# AutoReverse.net
KiCad netlist of a schematic drawn in Altium Designer
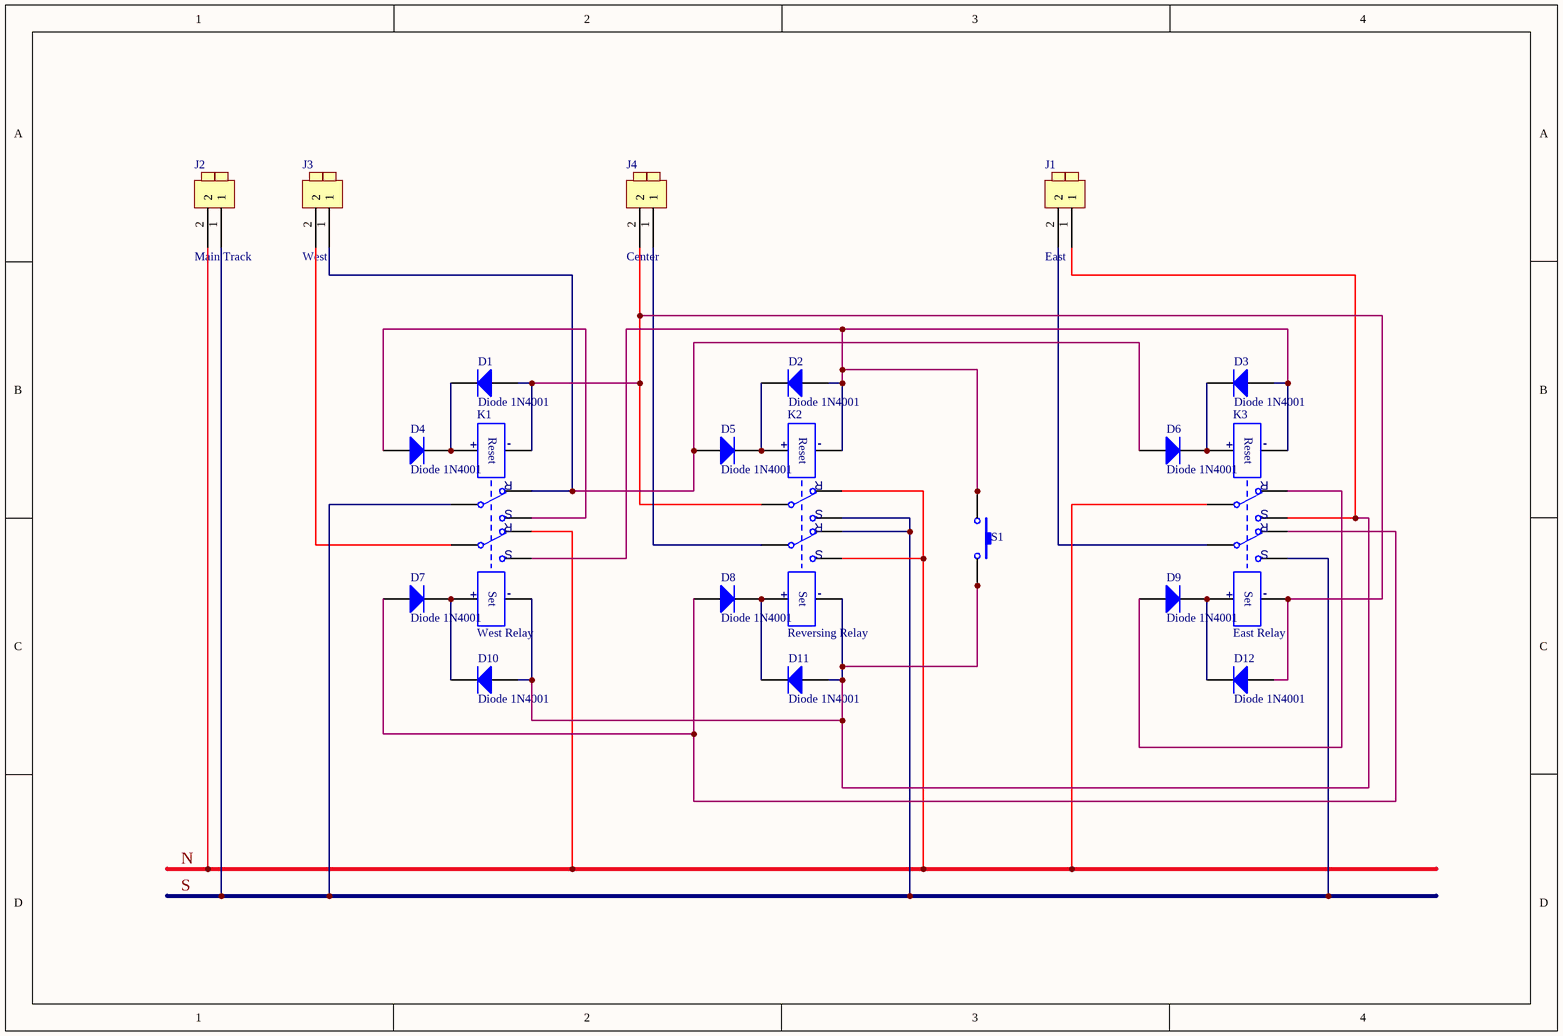
[diagram p0: AutoReverse.SchDoc]

(export (version "E")
  (design (tool "Eeschema 10.0.6"))
  (components
    (comp (ref "D1")
      (value "Diode 1N4001")
      (footprint "AXIAL-0.3")
      (description "1 Amp General Purpose Rectifier")
      (fields (field (name "PUBLISHER") "Altium Limited"))
      (libsource (lib "Miscellaneous Devices") (part "Diode 1N4001"))
    )
    (comp (ref "D2")
      (value "Diode 1N4001")
      (footprint "AXIAL-0.3")
      (description "1 Amp General Purpose Rectifier")
      (fields (field (name "PUBLISHER") "Altium Limited"))
      (libsource (lib "Miscellaneous Devices") (part "Diode 1N4001"))
    )
    (comp (ref "D3")
      (value "Diode 1N4001")
      (footprint "AXIAL-0.3")
      (description "1 Amp General Purpose Rectifier")
      (fields (field (name "PUBLISHER") "Altium Limited"))
      (libsource (lib "Miscellaneous Devices") (part "Diode 1N4001"))
    )
    (comp (ref "D4")
      (value "Diode 1N4001")
      (footprint "AXIAL-0.3")
      (description "1 Amp General Purpose Rectifier")
      (fields (field (name "PUBLISHER") "Altium Limited"))
      (libsource (lib "Miscellaneous Devices") (part "Diode 1N4001"))
    )
    (comp (ref "D5")
      (value "Diode 1N4001")
      (footprint "AXIAL-0.3")
      (description "1 Amp General Purpose Rectifier")
      (fields (field (name "PUBLISHER") "Altium Limited"))
      (libsource (lib "Miscellaneous Devices") (part "Diode 1N4001"))
    )
    (comp (ref "D6")
      (value "Diode 1N4001")
      (footprint "AXIAL-0.3")
      (description "1 Amp General Purpose Rectifier")
      (fields (field (name "PUBLISHER") "Altium Limited"))
      (libsource (lib "Miscellaneous Devices") (part "Diode 1N4001"))
    )
    (comp (ref "D7")
      (value "Diode 1N4001")
      (footprint "AXIAL-0.3")
      (description "1 Amp General Purpose Rectifier")
      (fields (field (name "PUBLISHER") "Altium Limited"))
      (libsource (lib "Miscellaneous Devices") (part "Diode 1N4001"))
    )
    (comp (ref "D8")
      (value "Diode 1N4001")
      (footprint "AXIAL-0.3")
      (description "1 Amp General Purpose Rectifier")
      (fields (field (name "PUBLISHER") "Altium Limited"))
      (libsource (lib "Miscellaneous Devices") (part "Diode 1N4001"))
    )
    (comp (ref "D9")
      (value "Diode 1N4001")
      (footprint "AXIAL-0.3")
      (description "1 Amp General Purpose Rectifier")
      (fields (field (name "PUBLISHER") "Altium Limited"))
      (libsource (lib "Miscellaneous Devices") (part "Diode 1N4001"))
    )
    (comp (ref "D10")
      (value "Diode 1N4001")
      (footprint "AXIAL-0.3")
      (description "1 Amp General Purpose Rectifier")
      (fields (field (name "PUBLISHER") "Altium Limited"))
      (libsource (lib "Miscellaneous Devices") (part "Diode 1N4001"))
    )
    (comp (ref "D11")
      (value "Diode 1N4001")
      (footprint "AXIAL-0.3")
      (description "1 Amp General Purpose Rectifier")
      (fields (field (name "PUBLISHER") "Altium Limited"))
      (libsource (lib "Miscellaneous Devices") (part "Diode 1N4001"))
    )
    (comp (ref "D12")
      (value "Diode 1N4001")
      (footprint "AXIAL-0.3")
      (description "1 Amp General Purpose Rectifier")
      (fields (field (name "PUBLISHER") "Altium Limited"))
      (libsource (lib "Miscellaneous Devices") (part "Diode 1N4001"))
    )
    (comp (ref "J1")
      (value "East")
      (footprint "Screw Terminal 2 way 0.2")
      (libsource (lib "Custom") (part "Screw Terminal 2 Way"))
    )
    (comp (ref "J2")
      (value "Main Track")
      (footprint "Screw Terminal 2 way 0.2")
      (libsource (lib "Custom") (part "Screw Terminal 2 Way"))
    )
    (comp (ref "J3")
      (value "West")
      (footprint "Screw Terminal 2 way 0.2")
      (libsource (lib "Custom") (part "Screw Terminal 2 Way"))
    )
    (comp (ref "J4")
      (value "Center")
      (footprint "Screw Terminal 2 way 0.2")
      (libsource (lib "Custom") (part "Screw Terminal 2 Way"))
    )
    (comp (ref "K1")
      (value "West Relay")
      (footprint "DIP-10")
      (description "EA2-5T Dual Coil 5V Latching Relay")
      (fields (field (name "PUBLISHER") "Altium Limited"))
      (libsource (lib "Custom") (part "EA2-5T Dual Coil 5V Latching Relay"))
    )
    (comp (ref "K2")
      (value "Reversing Relay")
      (footprint "DIP-10")
      (description "EA2-5T Dual Coil 5V Latching Relay")
      (fields (field (name "PUBLISHER") "Altium Limited"))
      (libsource (lib "Custom") (part "EA2-5T Dual Coil 5V Latching Relay"))
    )
    (comp (ref "K3")
      (value "East Relay")
      (footprint "DIP-10")
      (description "EA2-5T Dual Coil 5V Latching Relay")
      (fields (field (name "PUBLISHER") "Altium Limited"))
      (libsource (lib "Custom") (part "EA2-5T Dual Coil 5V Latching Relay"))
    )
    (comp (ref "S1")
      (value "SPST Micro Pushbutton")
      (footprint "SPST Micro Tactile")
      (libsource (lib "Custom") (part "SPST Micro Pushbutton"))
    )
  )
  (nets
    (net (code "1") (name "/N") (class "Default")
      (node (ref "J2") (pin "2") (pinfunction "2_2") (pintype "passive"))
      (node (ref "K1") (pin "9") (pinfunction "R_9") (pintype "passive"))
      (node (ref "K2") (pin "2") (pinfunction "R_2") (pintype "passive"))
      (node (ref "K2") (pin "7") (pinfunction "S_7") (pintype "passive"))
      (node (ref "K3") (pin "3") (pinfunction "3_3") (pintype "passive"))
    )
    (net (code "2") (name "/S") (class "Default")
      (node (ref "J2") (pin "1") (pinfunction "1_1") (pintype "passive"))
      (node (ref "K1") (pin "3") (pinfunction "3_3") (pintype "passive"))
      (node (ref "K2") (pin "4") (pinfunction "S_4") (pintype "passive"))
      (node (ref "K2") (pin "9") (pinfunction "R_9") (pintype "passive"))
      (node (ref "K3") (pin "7") (pinfunction "S_7") (pintype "passive"))
    )
    (net (code "3") (name "Net-(D1-A)") (class "Default")
      (node (ref "D1") (pin "1") (pinfunction "A_1") (pintype "passive"))
      (node (ref "D12") (pin "1") (pinfunction "A_1") (pintype "passive"))
      (node (ref "J4") (pin "2") (pinfunction "2_2") (pintype "passive"))
      (node (ref "K1") (pin "6") (pintype "passive"))
      (node (ref "K2") (pin "3") (pinfunction "3_3") (pintype "passive"))
      (node (ref "K3") (pin "5") (pintype "passive"))
    )
    (net (code "4") (name "Net-(D1-K)") (class "Default")
      (node (ref "D1") (pin "2") (pinfunction "K_2") (pintype "passive"))
      (node (ref "D4") (pin "2") (pinfunction "K_2") (pintype "passive"))
      (node (ref "K1") (pin "10") (pintype "passive"))
    )
    (net (code "5") (name "Net-(D2-A)") (class "Default")
      (node (ref "D2") (pin "1") (pinfunction "A_1") (pintype "passive"))
      (node (ref "D3") (pin "1") (pinfunction "A_1") (pintype "passive"))
      (node (ref "K1") (pin "7") (pinfunction "S_7") (pintype "passive"))
      (node (ref "K2") (pin "6") (pintype "passive"))
      (node (ref "K3") (pin "6") (pintype "passive"))
      (node (ref "S1") (pin "1a") (pinfunction "1_1a") (pintype "passive"))
      (node (ref "S1") (pin "1b") (pinfunction "1_1b") (pintype "passive"))
    )
    (net (code "6") (name "Net-(D2-K)") (class "Default")
      (node (ref "D2") (pin "2") (pinfunction "K_2") (pintype "passive"))
      (node (ref "D5") (pin "2") (pinfunction "K_2") (pintype "passive"))
      (node (ref "K2") (pin "10") (pintype "passive"))
    )
    (net (code "7") (name "Net-(D3-K)") (class "Default")
      (node (ref "D3") (pin "2") (pinfunction "K_2") (pintype "passive"))
      (node (ref "D6") (pin "2") (pinfunction "K_2") (pintype "passive"))
      (node (ref "K3") (pin "10") (pintype "passive"))
    )
    (net (code "8") (name "Net-(D4-A)") (class "Default")
      (node (ref "D4") (pin "1") (pinfunction "A_1") (pintype "passive"))
      (node (ref "K1") (pin "4") (pinfunction "S_4") (pintype "passive"))
    )
    (net (code "9") (name "Net-(D5-A)") (class "Default")
      (node (ref "D5") (pin "1") (pinfunction "A_1") (pintype "passive"))
      (node (ref "D6") (pin "1") (pinfunction "A_1") (pintype "passive"))
      (node (ref "J3") (pin "1") (pinfunction "1_1") (pintype "passive"))
      (node (ref "K1") (pin "2") (pinfunction "R_2") (pintype "passive"))
    )
    (net (code "10") (name "Net-(D7-A)") (class "Default")
      (node (ref "D7") (pin "1") (pinfunction "A_1") (pintype "passive"))
      (node (ref "D8") (pin "1") (pinfunction "A_1") (pintype "passive"))
      (node (ref "K3") (pin "9") (pinfunction "R_9") (pintype "passive"))
    )
    (net (code "11") (name "Net-(D9-A)") (class "Default")
      (node (ref "D9") (pin "1") (pinfunction "A_1") (pintype "passive"))
      (node (ref "K3") (pin "2") (pinfunction "R_2") (pintype "passive"))
    )
    (net (code "12") (name "Net-(D10-A)") (class "Default")
      (node (ref "D10") (pin "1") (pinfunction "A_1") (pintype "passive"))
      (node (ref "D11") (pin "1") (pinfunction "A_1") (pintype "passive"))
      (node (ref "J1") (pin "1") (pinfunction "1_1") (pintype "passive"))
      (node (ref "K1") (pin "5") (pintype "passive"))
      (node (ref "K2") (pin "5") (pintype "passive"))
      (node (ref "K3") (pin "4") (pinfunction "S_4") (pintype "passive"))
      (node (ref "S1") (pin "2a") (pinfunction "2_2a") (pintype "passive"))
      (node (ref "S1") (pin "2b") (pinfunction "2_2b") (pintype "passive"))
    )
    (net (code "13") (name "Net-(D10-K)") (class "Default")
      (node (ref "D10") (pin "2") (pinfunction "K_2") (pintype "passive"))
      (node (ref "D7") (pin "2") (pinfunction "K_2") (pintype "passive"))
      (node (ref "K1") (pin "1") (pintype "passive"))
    )
    (net (code "14") (name "Net-(D11-K)") (class "Default")
      (node (ref "D11") (pin "2") (pinfunction "K_2") (pintype "passive"))
      (node (ref "D8") (pin "2") (pinfunction "K_2") (pintype "passive"))
      (node (ref "K2") (pin "1") (pintype "passive"))
    )
    (net (code "15") (name "Net-(D12-K)") (class "Default")
      (node (ref "D12") (pin "2") (pinfunction "K_2") (pintype "passive"))
      (node (ref "D9") (pin "2") (pinfunction "K_2") (pintype "passive"))
      (node (ref "K3") (pin "1") (pintype "passive"))
    )
    (net (code "16") (name "Net-(J1-Pad2)") (class "Default")
      (node (ref "J1") (pin "2") (pinfunction "2_2") (pintype "passive"))
      (node (ref "K3") (pin "8") (pinfunction "8_8") (pintype "passive"))
    )
    (net (code "17") (name "Net-(J3-Pad2)") (class "Default")
      (node (ref "J3") (pin "2") (pinfunction "2_2") (pintype "passive"))
      (node (ref "K1") (pin "8") (pinfunction "8_8") (pintype "passive"))
    )
    (net (code "18") (name "Net-(J4-Pad1)") (class "Default")
      (node (ref "J4") (pin "1") (pinfunction "1_1") (pintype "passive"))
      (node (ref "K2") (pin "8") (pinfunction "8_8") (pintype "passive"))
    )
  )
)
